# CommitV2_0.net
KiCad netlist of a schematic drawn in Altium Designer
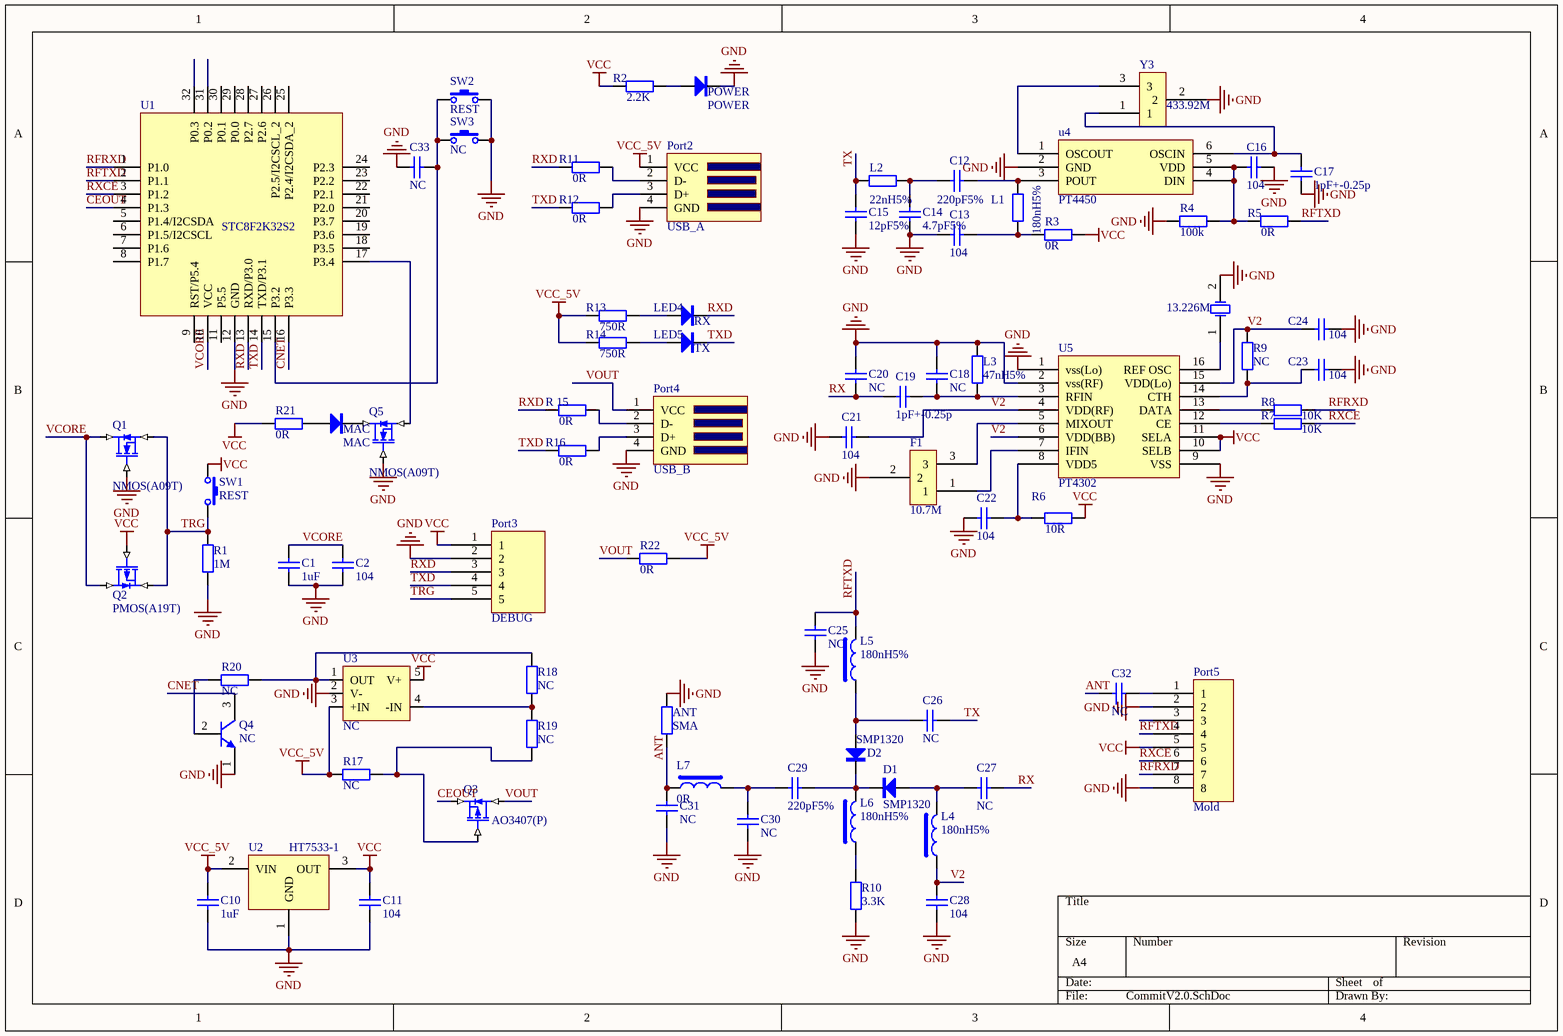
[diagram p0: CommitV2.0.SchDoc]

(export (version "E")
  (design (tool "Eeschema 10.0.6"))
  (components
    (comp (ref "ANT")
      (value "SMA")
      (footprint "SWA-KE天线母座")
      (description "Resistor")
      (fields (field (name "PUBLISHER") "Altium Limited"))
      (libsource (lib "") (part "Res2_2"))
    )
    (comp (ref "C1")
      (value "1uF")
      (footprint "0603")
      (description "Capacitor")
      (fields (field (name "PUBLISHER") "Altium Limited"))
      (libsource (lib "Miscellaneous Devices") (part "Cap"))
    )
    (comp (ref "C2")
      (value "104")
      (footprint "0603")
      (description "Capacitor")
      (fields (field (name "PUBLISHER") "Altium Limited"))
      (libsource (lib "Miscellaneous Devices") (part "Cap"))
    )
    (comp (ref "C10")
      (value "1uF")
      (footprint "0603")
      (description "Capacitor")
      (fields (field (name "PUBLISHER") "Altium Limited"))
      (libsource (lib "Miscellaneous Devices") (part "Cap"))
    )
    (comp (ref "C11")
      (value "104")
      (footprint "0603")
      (description "Capacitor")
      (fields (field (name "PUBLISHER") "Altium Limited"))
      (libsource (lib "Miscellaneous Devices") (part "Cap"))
    )
    (comp (ref "C12")
      (value "220pF5%")
      (footprint "0603")
      (description "Capacitor")
      (fields (field (name "PUBLISHER") "Altium Limited"))
      (libsource (lib "Miscellaneous Devices") (part "Cap"))
    )
    (comp (ref "C13")
      (value "104")
      (footprint "0603")
      (description "Capacitor")
      (fields (field (name "PUBLISHER") "Altium Limited"))
      (libsource (lib "Miscellaneous Devices") (part "Cap"))
    )
    (comp (ref "C14")
      (value "4.7pF5%")
      (footprint "0603")
      (description "Capacitor")
      (fields (field (name "PUBLISHER") "Altium Limited"))
      (libsource (lib "Miscellaneous Devices") (part "Cap"))
    )
    (comp (ref "C15")
      (value "12pF5%")
      (footprint "0603")
      (description "Capacitor")
      (fields (field (name "PUBLISHER") "Altium Limited"))
      (libsource (lib "Miscellaneous Devices") (part "Cap"))
    )
    (comp (ref "C16")
      (value "104")
      (footprint "0603")
      (description "Capacitor")
      (fields (field (name "PUBLISHER") "Altium Limited"))
      (libsource (lib "Miscellaneous Devices") (part "Cap"))
    )
    (comp (ref "C17")
      (value "1pF+-0.25p")
      (footprint "0603")
      (description "Capacitor")
      (fields (field (name "PUBLISHER") "Altium Limited"))
      (libsource (lib "Miscellaneous Devices") (part "Cap"))
    )
    (comp (ref "C18")
      (value "NC")
      (footprint "0603")
      (description "Capacitor")
      (fields (field (name "PUBLISHER") "Altium Limited"))
      (libsource (lib "Miscellaneous Devices") (part "Cap"))
    )
    (comp (ref "C19")
      (value "1pF+-0.25p")
      (footprint "0603")
      (description "Capacitor")
      (fields (field (name "PUBLISHER") "Altium Limited"))
      (libsource (lib "Miscellaneous Devices") (part "Cap"))
    )
    (comp (ref "C20")
      (value "NC")
      (footprint "0603")
      (description "Capacitor")
      (fields (field (name "PUBLISHER") "Altium Limited"))
      (libsource (lib "Miscellaneous Devices") (part "Cap"))
    )
    (comp (ref "C21")
      (value "104")
      (footprint "0603")
      (description "Capacitor")
      (fields (field (name "PUBLISHER") "Altium Limited"))
      (libsource (lib "Miscellaneous Devices") (part "Cap"))
    )
    (comp (ref "C22")
      (value "104")
      (footprint "0603")
      (description "Capacitor")
      (fields (field (name "PUBLISHER") "Altium Limited"))
      (libsource (lib "Miscellaneous Devices") (part "Cap"))
    )
    (comp (ref "C23")
      (value "104")
      (footprint "0603")
      (description "Capacitor")
      (fields (field (name "PUBLISHER") "Altium Limited"))
      (libsource (lib "Miscellaneous Devices") (part "Cap"))
    )
    (comp (ref "C24")
      (value "104")
      (footprint "0603")
      (description "Capacitor")
      (fields (field (name "PUBLISHER") "Altium Limited"))
      (libsource (lib "Miscellaneous Devices") (part "Cap"))
    )
    (comp (ref "C25")
      (value "NC")
      (footprint "0603")
      (description "Capacitor")
      (fields (field (name "PUBLISHER") "Altium Limited"))
      (libsource (lib "Miscellaneous Devices") (part "Cap"))
    )
    (comp (ref "C26")
      (value "NC")
      (footprint "0603")
      (description "Capacitor")
      (fields (field (name "PUBLISHER") "Altium Limited"))
      (libsource (lib "Miscellaneous Devices") (part "Cap"))
    )
    (comp (ref "C27")
      (value "NC")
      (footprint "0603")
      (description "Capacitor")
      (fields (field (name "PUBLISHER") "Altium Limited"))
      (libsource (lib "Miscellaneous Devices") (part "Cap"))
    )
    (comp (ref "C28")
      (value "104")
      (footprint "0603")
      (description "Capacitor")
      (fields (field (name "PUBLISHER") "Altium Limited"))
      (libsource (lib "Miscellaneous Devices") (part "Cap"))
    )
    (comp (ref "C29")
      (value "220pF5%")
      (footprint "0603")
      (description "Capacitor")
      (fields (field (name "PUBLISHER") "Altium Limited"))
      (libsource (lib "Miscellaneous Devices") (part "Cap"))
    )
    (comp (ref "C30")
      (value "NC")
      (footprint "0603")
      (description "Capacitor")
      (fields (field (name "PUBLISHER") "Altium Limited"))
      (libsource (lib "Miscellaneous Devices") (part "Cap"))
    )
    (comp (ref "C31")
      (value "NC")
      (footprint "0603")
      (description "Capacitor")
      (fields (field (name "PUBLISHER") "Altium Limited"))
      (libsource (lib "Miscellaneous Devices") (part "Cap"))
    )
    (comp (ref "C32")
      (value "NC")
      (footprint "0603")
      (description "Capacitor")
      (fields (field (name "PUBLISHER") "Altium Limited"))
      (libsource (lib "Miscellaneous Devices") (part "Cap"))
    )
    (comp (ref "C33")
      (value "NC")
      (footprint "0603")
      (description "Capacitor")
      (fields (field (name "PUBLISHER") "Altium Limited"))
      (libsource (lib "Miscellaneous Devices") (part "Cap"))
    )
    (comp (ref "D1")
      (value "SMP1320")
      (footprint "0603")
      (description "diode")
      (libsource (lib "") (part "DIODE_2"))
    )
    (comp (ref "D2")
      (value "SMP1320")
      (footprint "0603")
      (description "diode")
      (libsource (lib "") (part "DIODE_1"))
    )
    (comp (ref "F1") (value "10.7M") (footprint "PT4450 XTAL") (libsource (lib "MYSHC") (part "Filter")))
    (comp (ref "L1")
      (value "180nH5%")
      (footprint "0603")
      (description "Resistor")
      (fields (field (name "PUBLISHER") "Altium Limited"))
      (libsource (lib "Miscellaneous Devices") (part "Res2"))
    )
    (comp (ref "L2")
      (value "22nH5%")
      (footprint "0603")
      (description "Resistor")
      (fields (field (name "PUBLISHER") "Altium Limited"))
      (libsource (lib "") (part "Res2_3"))
    )
    (comp (ref "L3")
      (value "47nH5%")
      (footprint "0603")
      (description "Resistor")
      (fields (field (name "PUBLISHER") "Altium Limited"))
      (libsource (lib "") (part "Res2_2"))
    )
    (comp (ref "L4")
      (value "180nH5%")
      (footprint "0603")
      (description "Inductor")
      (libsource (lib "") (part "L_1"))
    )
    (comp (ref "L5")
      (value "180nH5%")
      (footprint "0603")
      (description "Inductor")
      (libsource (lib "") (part "L_1"))
    )
    (comp (ref "L6")
      (value "180nH5%")
      (footprint "0603")
      (description "Inductor")
      (libsource (lib "") (part "L_1"))
    )
    (comp (ref "L7")
      (value "0R")
      (footprint "0603")
      (description "Inductor")
      (libsource (lib "dajiang SCH -DXP") (part "L"))
    )
    (comp (ref "LED4")
      (value "RX")
      (footprint "LED-0603")
      (description "diode")
      (libsource (lib "dajiang SCH -DXP") (part "DIODE"))
    )
    (comp (ref "LED5")
      (value "TX")
      (footprint "LED-0603")
      (description "diode")
      (libsource (lib "dajiang SCH -DXP") (part "DIODE"))
    )
    (comp (ref "MAC")
      (value "MAC")
      (footprint "2.54LED")
      (description "diode")
      (libsource (lib "dajiang SCH -DXP") (part "DIODE"))
    )
    (comp (ref "Port2") (value "USB_A") (footprint "USB-A") (libsource (lib "mylib") (part "USB")))
    (comp (ref "Port3") (value "DEBUG") (footprint "STC_DEBUG") (libsource (lib "MYSHC") (part "PIN-5")))
    (comp (ref "Port4") (value "USB_B") (footprint "USB-A") (libsource (lib "mylib") (part "USB")))
    (comp (ref "Port5") (value "Mold") (footprint "Pin-8") (libsource (lib "MYSHC") (part "Pin-8")))
    (comp (ref "POWER")
      (value "POWER")
      (footprint "2.54LED")
      (description "diode")
      (libsource (lib "dajiang SCH -DXP") (part "DIODE"))
    )
    (comp (ref "Q1")
      (value "NMOS(A09T)")
      (footprint "SOT-23")
      (description "mosfet")
      (libsource (lib "dajiang SCH -DXP") (part "MOSFET-N"))
    )
    (comp (ref "Q2")
      (value "PMOS(A19T)")
      (footprint "SOT-23")
      (description "mosfet")
      (libsource (lib "dajiang SCH -DXP") (part "MOSFET-P"))
    )
    (comp (ref "Q3")
      (value "AO3407(P)")
      (footprint "SOT-23")
      (description "mosfet")
      (libsource (lib "dajiang SCH -DXP") (part "MOSFET-P"))
    )
    (comp (ref "Q4")
      (value "NC")
      (footprint "SOT-23")
      (description "NPN General Purpose Amplifier")
      (fields (field (name "PUBLISHER") "Altium Limited"))
      (libsource (lib "DT-852A(3)") (part "2N3904"))
    )
    (comp (ref "Q5")
      (value "NMOS(A09T)")
      (footprint "SOT-23")
      (description "mosfet")
      (libsource (lib "dajiang SCH -DXP") (part "MOSFET-N"))
    )
    (comp (ref "R 15")
      (value "0R")
      (footprint "0603")
      (description "Resistor")
      (fields (field (name "PUBLISHER") "Altium Limited"))
      (libsource (lib "") (part "Res2_1"))
    )
    (comp (ref "R1")
      (value "1M")
      (footprint "0603")
      (description "Resistor")
      (fields (field (name "PUBLISHER") "Altium Limited"))
      (libsource (lib "") (part "Res2_2"))
    )
    (comp (ref "R2")
      (value "2.2K")
      (footprint "0603")
      (description "Resistor")
      (fields (field (name "PUBLISHER") "Altium Limited"))
      (libsource (lib "") (part "Res2_1"))
    )
    (comp (ref "R3")
      (value "0R")
      (footprint "0603")
      (description "Resistor")
      (fields (field (name "PUBLISHER") "Altium Limited"))
      (libsource (lib "") (part "Res2_1"))
    )
    (comp (ref "R4")
      (value "100k")
      (footprint "0603")
      (description "Resistor")
      (fields (field (name "PUBLISHER") "Altium Limited"))
      (libsource (lib "") (part "Res2_1"))
    )
    (comp (ref "R5")
      (value "0R")
      (footprint "0603")
      (description "Resistor")
      (fields (field (name "PUBLISHER") "Altium Limited"))
      (libsource (lib "") (part "Res2_1"))
    )
    (comp (ref "R6")
      (value "10R")
      (footprint "0603")
      (description "Resistor")
      (fields (field (name "PUBLISHER") "Altium Limited"))
      (libsource (lib "") (part "Res2_1"))
    )
    (comp (ref "R7")
      (value "10K")
      (footprint "0603")
      (description "Resistor")
      (fields (field (name "PUBLISHER") "Altium Limited"))
      (libsource (lib "") (part "Res2_1"))
    )
    (comp (ref "R8")
      (value "10K")
      (footprint "0603")
      (description "Resistor")
      (fields (field (name "PUBLISHER") "Altium Limited"))
      (libsource (lib "") (part "Res2_1"))
    )
    (comp (ref "R9")
      (value "NC")
      (footprint "0603")
      (description "Resistor")
      (fields (field (name "PUBLISHER") "Altium Limited"))
      (libsource (lib "Miscellaneous Devices") (part "Res2"))
    )
    (comp (ref "R10")
      (value "3.3K")
      (footprint "0603")
      (description "Resistor")
      (fields (field (name "PUBLISHER") "Altium Limited"))
      (libsource (lib "Miscellaneous Devices") (part "Res2"))
    )
    (comp (ref "R11")
      (value "0R")
      (footprint "0603")
      (description "Resistor")
      (fields (field (name "PUBLISHER") "Altium Limited"))
      (libsource (lib "") (part "Res2_1"))
    )
    (comp (ref "R12")
      (value "0R")
      (footprint "0603")
      (description "Resistor")
      (fields (field (name "PUBLISHER") "Altium Limited"))
      (libsource (lib "") (part "Res2_1"))
    )
    (comp (ref "R13")
      (value "750R")
      (footprint "0603")
      (description "Resistor")
      (fields (field (name "PUBLISHER") "Altium Limited"))
      (libsource (lib "") (part "Res2_1"))
    )
    (comp (ref "R14")
      (value "750R")
      (footprint "0603")
      (description "Resistor")
      (fields (field (name "PUBLISHER") "Altium Limited"))
      (libsource (lib "") (part "Res2_1"))
    )
    (comp (ref "R16")
      (value "0R")
      (footprint "0603")
      (description "Resistor")
      (fields (field (name "PUBLISHER") "Altium Limited"))
      (libsource (lib "") (part "Res2_1"))
    )
    (comp (ref "R17")
      (value "NC")
      (footprint "0603")
      (description "Resistor")
      (fields (field (name "PUBLISHER") "Altium Limited"))
      (libsource (lib "") (part "Res2_1"))
    )
    (comp (ref "R18")
      (value "NC")
      (footprint "0603")
      (description "Resistor")
      (fields (field (name "PUBLISHER") "Altium Limited"))
      (libsource (lib "") (part "Res2_2"))
    )
    (comp (ref "R19")
      (value "NC")
      (footprint "0603")
      (description "Resistor")
      (fields (field (name "PUBLISHER") "Altium Limited"))
      (libsource (lib "") (part "Res2_2"))
    )
    (comp (ref "R20")
      (value "NC")
      (footprint "0603")
      (description "Resistor")
      (fields (field (name "PUBLISHER") "Altium Limited"))
      (libsource (lib "") (part "Res2_1"))
    )
    (comp (ref "R21")
      (value "0R")
      (footprint "0603")
      (description "Resistor")
      (fields (field (name "PUBLISHER") "Altium Limited"))
      (libsource (lib "") (part "Res2_1"))
    )
    (comp (ref "R22")
      (value "0R")
      (footprint "0805")
      (description "Resistor")
      (fields (field (name "PUBLISHER") "Altium Limited"))
      (libsource (lib "") (part "Res2_1"))
    )
    (comp (ref "SW1")
      (value "REST")
      (footprint "SW-1")
      (description "key")
      (libsource (lib "dajiang SCH -DXP") (part "SW-P"))
    )
    (comp (ref "SW2")
      (value "REST")
      (footprint "Key1")
      (description "key")
      (libsource (lib "dajiang SCH -DXP") (part "SW-P"))
    )
    (comp (ref "SW3")
      (value "NC")
      (footprint "Key1")
      (description "key")
      (libsource (lib "dajiang SCH -DXP") (part "SW-P"))
    )
    (comp (ref "U1")
      (value "STC8F2K32S2")
      (footprint "LQPF-32")
      (libsource (lib "mylib") (part "STC8F2K64S2"))
    )
    (comp (ref "U2") (value "HT7533-1") (footprint "3A5A3D") (libsource (lib "mylib") (part "HT7533-1")))
    (comp (ref "U3") (value "NC") (footprint "AD8628") (libsource (lib "*") (part "AD8628")))
    (comp (ref "u4") (value "PT4450") (libsource (lib "MYSHC") (part "PT4450")))
    (comp (ref "U5") (value "PT4302") (footprint "PT4302") (libsource (lib "MYSHC") (part "PT4302")))
    (comp (ref "Y3")
      (value "433.92M")
      (footprint "PT4450 XTAL")
      (libsource (lib "MYSHC") (part "PT4450-XTAL"))
    )
    (comp (ref "Y4")
      (value "13.226M")
      (footprint "PT4306 XTAL")
      (description "Crystal Oscillator")
      (libsource (lib "DT-852A(3)") (part "XTAL"))
    )
  )
  (nets
    (net (code "1") (name "/ANT") (class "Default")
      (node (ref "ANT") (pin "1") (pinfunction "1_1") (pintype "passive"))
      (node (ref "C31") (pin "1") (pinfunction "1_1") (pintype "passive"))
      (node (ref "C32") (pin "1") (pinfunction "1_1") (pintype "passive"))
      (node (ref "L7") (pin "1") (pinfunction "1_1") (pintype "passive"))
    )
    (net (code "2") (name "/CEOUT") (class "Default")
      (node (ref "Q3") (pin "2") (pinfunction "S_2") (pintype "input"))
      (node (ref "U1") (pin "4") (pinfunction "P1.3_4") (pintype "passive"))
    )
    (net (code "3") (name "/CNET") (class "Default")
      (node (ref "Q4") (pin "3") (pinfunction "C_3") (pintype "passive"))
      (node (ref "U1") (pin "16") (pinfunction "P3.3_16") (pintype "passive"))
    )
    (net (code "4") (name "/RFRXD") (class "Default")
      (node (ref "Port5") (pin "7") (pinfunction "7_7") (pintype "passive"))
      (node (ref "R8") (pin "1") (pinfunction "1_1") (pintype "passive"))
      (node (ref "U1") (pin "1") (pinfunction "P1.0_1") (pintype "passive"))
    )
    (net (code "5") (name "/RFTXD") (class "Default")
      (node (ref "C25") (pin "1") (pinfunction "1_1") (pintype "passive"))
      (node (ref "L5") (pin "2") (pinfunction "2_2") (pintype "passive"))
      (node (ref "Port5") (pin "4") (pinfunction "4_4") (pintype "passive"))
      (node (ref "R5") (pin "1") (pinfunction "1_1") (pintype "passive"))
      (node (ref "U1") (pin "2") (pinfunction "P1.1_2") (pintype "passive"))
    )
    (net (code "6") (name "/RX") (class "Default")
      (node (ref "C19") (pin "1") (pinfunction "1_1") (pintype "passive"))
      (node (ref "C20") (pin "1") (pinfunction "1_1") (pintype "passive"))
      (node (ref "C27") (pin "2") (pinfunction "2_2") (pintype "passive"))
    )
    (net (code "7") (name "/RXCE") (class "Default")
      (node (ref "Port5") (pin "6") (pinfunction "6_6") (pintype "passive"))
      (node (ref "R7") (pin "1") (pinfunction "1_1") (pintype "passive"))
      (node (ref "U1") (pin "3") (pinfunction "P1.2_3") (pintype "passive"))
    )
    (net (code "8") (name "/RXD") (class "Default")
      (node (ref "LED4") (pin "2") (pinfunction "2_2") (pintype "passive"))
      (node (ref "Port3") (pin "3") (pinfunction "3_3") (pintype "passive"))
      (node (ref "R 15") (pin "2") (pinfunction "2_2") (pintype "passive"))
      (node (ref "R11") (pin "2") (pinfunction "2_2") (pintype "passive"))
      (node (ref "U1") (pin "13") (pinfunction "RXD/P3.0_13") (pintype "passive"))
    )
    (net (code "9") (name "/TRG") (class "Default")
      (node (ref "Port3") (pin "5") (pinfunction "5_5") (pintype "passive"))
      (node (ref "Q1") (pin "2") (pinfunction "D_2") (pintype "input"))
      (node (ref "Q2") (pin "2") (pinfunction "S_2") (pintype "input"))
      (node (ref "R1") (pin "2") (pinfunction "2_2") (pintype "passive"))
      (node (ref "SW1") (pin "2") (pinfunction "2_2") (pintype "passive"))
    )
    (net (code "10") (name "/TX") (class "Default")
      (node (ref "C15") (pin "2") (pinfunction "2_2") (pintype "passive"))
      (node (ref "C26") (pin "2") (pinfunction "2_2") (pintype "passive"))
      (node (ref "L2") (pin "1") (pinfunction "1_1") (pintype "passive"))
    )
    (net (code "11") (name "/TXD") (class "Default")
      (node (ref "LED5") (pin "2") (pinfunction "2_2") (pintype "passive"))
      (node (ref "Port3") (pin "4") (pinfunction "4_4") (pintype "passive"))
      (node (ref "R12") (pin "2") (pinfunction "2_2") (pintype "passive"))
      (node (ref "R16") (pin "2") (pinfunction "2_2") (pintype "passive"))
      (node (ref "U1") (pin "14") (pinfunction "TXD/P3.1_14") (pintype "passive"))
    )
    (net (code "12") (name "/V2") (class "Default")
      (node (ref "C21") (pin "1") (pinfunction "1_1") (pintype "passive"))
      (node (ref "C24") (pin "2") (pinfunction "2_2") (pintype "passive"))
      (node (ref "C28") (pin "2") (pinfunction "2_2") (pintype "passive"))
      (node (ref "L4") (pin "1") (pinfunction "1_1") (pintype "passive"))
      (node (ref "R9") (pin "1") (pinfunction "1_1") (pintype "passive"))
      (node (ref "U5") (pin "15") (pinfunction "VDD(Lo)_15") (pintype "passive"))
      (node (ref "U5") (pin "4") (pinfunction "VDD(RF)_4") (pintype "passive"))
      (node (ref "U5") (pin "6") (pinfunction "VDD(BB)_6") (pintype "passive"))
    )
    (net (code "13") (name "/VCORE") (class "Default")
      (node (ref "C1") (pin "2") (pinfunction "2_2") (pintype "passive"))
      (node (ref "C2") (pin "2") (pinfunction "2_2") (pintype "passive"))
      (node (ref "Q1") (pin "3") (pinfunction "S_3") (pintype "input"))
      (node (ref "Q2") (pin "3") (pinfunction "D_3") (pintype "input"))
      (node (ref "U1") (pin "10") (pinfunction "VCC_10") (pintype "passive"))
    )
    (net (code "14") (name "/VOUT") (class "Default")
      (node (ref "Port4") (pin "1") (pinfunction "VCC_1") (pintype "passive"))
      (node (ref "Q3") (pin "3") (pinfunction "D_3") (pintype "input"))
      (node (ref "R22") (pin "2") (pinfunction "2_2") (pintype "passive"))
    )
    (net (code "15") (name "GND") (class "Default")
      (node (ref "ANT") (pin "2") (pinfunction "2_2") (pintype "passive"))
      (node (ref "C1") (pin "1") (pinfunction "1_1") (pintype "passive"))
      (node (ref "C10") (pin "2") (pinfunction "2_2") (pintype "passive"))
      (node (ref "C11") (pin "2") (pinfunction "2_2") (pintype "passive"))
      (node (ref "C13") (pin "1") (pinfunction "1_1") (pintype "passive"))
      (node (ref "C14") (pin "1") (pinfunction "1_1") (pintype "passive"))
      (node (ref "C15") (pin "1") (pinfunction "1_1") (pintype "passive"))
      (node (ref "C16") (pin "1") (pinfunction "1_1") (pintype "passive"))
      (node (ref "C17") (pin "2") (pinfunction "2_2") (pintype "passive"))
      (node (ref "C18") (pin "1") (pinfunction "1_1") (pintype "passive"))
      (node (ref "C2") (pin "1") (pinfunction "1_1") (pintype "passive"))
      (node (ref "C20") (pin "2") (pinfunction "2_2") (pintype "passive"))
      (node (ref "C21") (pin "2") (pinfunction "2_2") (pintype "passive"))
      (node (ref "C22") (pin "2") (pinfunction "2_2") (pintype "passive"))
      (node (ref "C23") (pin "1") (pinfunction "1_1") (pintype "passive"))
      (node (ref "C24") (pin "1") (pinfunction "1_1") (pintype "passive"))
      (node (ref "C25") (pin "2") (pinfunction "2_2") (pintype "passive"))
      (node (ref "C28") (pin "1") (pinfunction "1_1") (pintype "passive"))
      (node (ref "C30") (pin "2") (pinfunction "2_2") (pintype "passive"))
      (node (ref "C31") (pin "2") (pinfunction "2_2") (pintype "passive"))
      (node (ref "C33") (pin "1") (pinfunction "1_1") (pintype "passive"))
      (node (ref "F1") (pin "2") (pinfunction "2_2") (pintype "passive"))
      (node (ref "L3") (pin "2") (pinfunction "2_2") (pintype "passive"))
      (node (ref "POWER") (pin "2") (pinfunction "2_2") (pintype "passive"))
      (node (ref "Port2") (pin "4") (pinfunction "GND_4") (pintype "passive"))
      (node (ref "Port3") (pin "2") (pinfunction "2_2") (pintype "passive"))
      (node (ref "Port4") (pin "4") (pinfunction "GND_4") (pintype "passive"))
      (node (ref "Port5") (pin "2") (pinfunction "2_2") (pintype "passive"))
      (node (ref "Port5") (pin "8") (pinfunction "8_8") (pintype "passive"))
      (node (ref "Q1") (pin "1") (pinfunction "G_1") (pintype "input"))
      (node (ref "Q4") (pin "1") (pinfunction "E_1") (pintype "passive"))
      (node (ref "Q5") (pin "1") (pinfunction "G_1") (pintype "input"))
      (node (ref "R1") (pin "1") (pinfunction "1_1") (pintype "passive"))
      (node (ref "R10") (pin "2") (pinfunction "2_2") (pintype "passive"))
      (node (ref "R4") (pin "2") (pinfunction "2_2") (pintype "passive"))
      (node (ref "SW2") (pin "2") (pinfunction "2_2") (pintype "passive"))
      (node (ref "SW3") (pin "2") (pinfunction "2_2") (pintype "passive"))
      (node (ref "U1") (pin "12") (pinfunction "GND_12") (pintype "passive"))
      (node (ref "U2") (pin "1") (pinfunction "GND_1") (pintype "passive"))
      (node (ref "U3") (pin "2") (pinfunction "V-_2") (pintype "passive"))
      (node (ref "U5") (pin "1") (pinfunction "vss(Lo)_1") (pintype "passive"))
      (node (ref "U5") (pin "2") (pinfunction "vss(RF)_2") (pintype "passive"))
      (node (ref "U5") (pin "9") (pinfunction "VSS_9") (pintype "passive"))
      (node (ref "Y3") (pin "2") (pinfunction "2_2") (pintype "passive"))
      (node (ref "Y4") (pin "2") (pinfunction "OSC2_2") (pintype "passive"))
      (node (ref "u4") (pin "2") (pinfunction "GND_2") (pintype "passive"))
    )
    (net (code "16") (name "Net-(C12-Pad1)") (class "Default")
      (node (ref "C12") (pin "1") (pinfunction "1_1") (pintype "passive"))
      (node (ref "C14") (pin "2") (pinfunction "2_2") (pintype "passive"))
      (node (ref "L2") (pin "2") (pinfunction "2_2") (pintype "passive"))
    )
    (net (code "17") (name "Net-(C13-Pad2)") (class "Default")
      (node (ref "C13") (pin "2") (pinfunction "2_2") (pintype "passive"))
      (node (ref "L1") (pin "2") (pinfunction "2_2") (pintype "passive"))
      (node (ref "R3") (pin "2") (pinfunction "2_2") (pintype "passive"))
    )
    (net (code "18") (name "Net-(C26-Pad1)") (class "Default")
      (node (ref "C26") (pin "1") (pinfunction "1_1") (pintype "passive"))
      (node (ref "D2") (pin "1") (pinfunction "1_1") (pintype "passive"))
      (node (ref "L5") (pin "1") (pinfunction "1_1") (pintype "passive"))
    )
    (net (code "19") (name "Net-(C27-Pad1)") (class "Default")
      (node (ref "C27") (pin "1") (pinfunction "1_1") (pintype "passive"))
      (node (ref "D1") (pin "1") (pinfunction "1_1") (pintype "passive"))
      (node (ref "L4") (pin "2") (pinfunction "2_2") (pintype "passive"))
    )
    (net (code "20") (name "Net-(C29-Pad1)") (class "Default")
      (node (ref "C29") (pin "1") (pinfunction "1_1") (pintype "passive"))
      (node (ref "D1") (pin "2") (pinfunction "2_2") (pintype "passive"))
      (node (ref "D2") (pin "2") (pinfunction "2_2") (pintype "passive"))
      (node (ref "L6") (pin "2") (pinfunction "2_2") (pintype "passive"))
    )
    (net (code "21") (name "Net-(C29-Pad2)") (class "Default")
      (node (ref "C29") (pin "2") (pinfunction "2_2") (pintype "passive"))
      (node (ref "C30") (pin "1") (pinfunction "1_1") (pintype "passive"))
      (node (ref "L7") (pin "2") (pinfunction "2_2") (pintype "passive"))
    )
    (net (code "22") (name "Net-(C32-Pad2)") (class "Default")
      (node (ref "C32") (pin "2") (pinfunction "2_2") (pintype "passive"))
      (node (ref "Port5") (pin "1") (pinfunction "1_1") (pintype "passive"))
    )
    (net (code "23") (name "Net-(L6-Pad1)") (class "Default")
      (node (ref "L6") (pin "1") (pinfunction "1_1") (pintype "passive"))
      (node (ref "R10") (pin "1") (pinfunction "1_1") (pintype "passive"))
    )
    (net (code "24") (name "Net-(LED4-Pad1)") (class "Default")
      (node (ref "LED4") (pin "1") (pinfunction "1_1") (pintype "passive"))
      (node (ref "R13") (pin "1") (pinfunction "1_1") (pintype "passive"))
    )
    (net (code "25") (name "Net-(LED5-Pad1)") (class "Default")
      (node (ref "LED5") (pin "1") (pinfunction "1_1") (pintype "passive"))
      (node (ref "R14") (pin "1") (pinfunction "1_1") (pintype "passive"))
    )
    (net (code "26") (name "Net-(MAC-Pad1)") (class "Default")
      (node (ref "MAC") (pin "1") (pinfunction "1_1") (pintype "passive"))
      (node (ref "R21") (pin "1") (pinfunction "1_1") (pintype "passive"))
    )
    (net (code "27") (name "Net-(POWER-Pad1)") (class "Default")
      (node (ref "POWER") (pin "1") (pinfunction "1_1") (pintype "passive"))
      (node (ref "R2") (pin "1") (pinfunction "1_1") (pintype "passive"))
    )
    (net (code "28") (name "Net-(Port2-D+)") (class "Default")
      (node (ref "Port2") (pin "3") (pinfunction "D+_3") (pintype "passive"))
      (node (ref "R12") (pin "1") (pinfunction "1_1") (pintype "passive"))
    )
    (net (code "29") (name "Net-(Port2-D-)") (class "Default")
      (node (ref "Port2") (pin "2") (pinfunction "D-_2") (pintype "passive"))
      (node (ref "R11") (pin "1") (pinfunction "1_1") (pintype "passive"))
    )
    (net (code "30") (name "Net-(Port4-D+)") (class "Default")
      (node (ref "Port4") (pin "3") (pinfunction "D+_3") (pintype "passive"))
      (node (ref "R16") (pin "1") (pinfunction "1_1") (pintype "passive"))
    )
    (net (code "31") (name "Net-(Port4-D-)") (class "Default")
      (node (ref "Port4") (pin "2") (pinfunction "D-_2") (pintype "passive"))
      (node (ref "R 15") (pin "1") (pinfunction "1_1") (pintype "passive"))
    )
    (net (code "32") (name "Net-(Q3-G)") (class "Default")
      (node (ref "Q3") (pin "1") (pinfunction "G_1") (pintype "input"))
      (node (ref "R17") (pin "1") (pinfunction "1_1") (pintype "passive"))
      (node (ref "R19") (pin "1") (pinfunction "1_1") (pintype "passive"))
    )
    (net (code "33") (name "Net-(Q4-B)") (class "Default")
      (node (ref "Q4") (pin "2") (pinfunction "B_2") (pintype "passive"))
      (node (ref "R20") (pin "2") (pinfunction "2_2") (pintype "passive"))
    )
    (net (code "34") (name "Net-(Q5-D)") (class "Default")
      (node (ref "Q5") (pin "2") (pinfunction "D_2") (pintype "input"))
      (node (ref "U1") (pin "17") (pinfunction "P3.4_17") (pintype "passive"))
    )
    (net (code "35") (name "Net-(Q5-S)") (class "Default")
      (node (ref "MAC") (pin "2") (pinfunction "2_2") (pintype "passive"))
      (node (ref "Q5") (pin "3") (pinfunction "S_3") (pintype "input"))
    )
    (net (code "36") (name "Net-(U1-P3.2)") (class "Default")
      (node (ref "C33") (pin "2") (pinfunction "2_2") (pintype "passive"))
      (node (ref "SW2") (pin "1") (pinfunction "1_1") (pintype "passive"))
      (node (ref "SW3") (pin "1") (pinfunction "1_1") (pintype "passive"))
      (node (ref "U1") (pin "15") (pinfunction "P3.2_15") (pintype "passive"))
    )
    (net (code "37") (name "Net-(U3--IN)") (class "Default")
      (node (ref "R18") (pin "1") (pinfunction "1_1") (pintype "passive"))
      (node (ref "R19") (pin "2") (pinfunction "2_2") (pintype "passive"))
      (node (ref "U3") (pin "4") (pinfunction "-IN_4") (pintype "passive"))
    )
    (net (code "38") (name "Net-(U3-OUT)") (class "Default")
      (node (ref "R18") (pin "2") (pinfunction "2_2") (pintype "passive"))
      (node (ref "R20") (pin "1") (pinfunction "1_1") (pintype "passive"))
      (node (ref "U3") (pin "1") (pinfunction "OUT_1") (pintype "passive"))
    )
    (net (code "39") (name "Net-(U5-CE)") (class "Default")
      (node (ref "R7") (pin "2") (pinfunction "2_2") (pintype "passive"))
      (node (ref "U5") (pin "12") (pinfunction "CE_12") (pintype "passive"))
    )
    (net (code "40") (name "Net-(U5-CTH)") (class "Default")
      (node (ref "C23") (pin "2") (pinfunction "2_2") (pintype "passive"))
      (node (ref "R9") (pin "2") (pinfunction "2_2") (pintype "passive"))
      (node (ref "U5") (pin "14") (pinfunction "CTH_14") (pintype "passive"))
    )
    (net (code "41") (name "Net-(U5-DATA)") (class "Default")
      (node (ref "R8") (pin "2") (pinfunction "2_2") (pintype "passive"))
      (node (ref "U5") (pin "13") (pinfunction "DATA_13") (pintype "passive"))
    )
    (net (code "42") (name "Net-(U5-IFIN)") (class "Default")
      (node (ref "F1") (pin "1") (pinfunction "1_1") (pintype "passive"))
      (node (ref "U5") (pin "7") (pinfunction "IFIN_7") (pintype "passive"))
    )
    (net (code "43") (name "Net-(U5-MIXOUT)") (class "Default")
      (node (ref "F1") (pin "3") (pinfunction "3_3") (pintype "passive"))
      (node (ref "U5") (pin "5") (pinfunction "MIXOUT_5") (pintype "passive"))
    )
    (net (code "44") (name "Net-(U5-REF_OSC)") (class "Default")
      (node (ref "U5") (pin "16") (pinfunction "REF_OSC_16") (pintype "passive"))
      (node (ref "Y4") (pin "1") (pinfunction "OSC1_1") (pintype "passive"))
    )
    (net (code "45") (name "Net-(U5-RFIN)") (class "Default")
      (node (ref "C18") (pin "2") (pinfunction "2_2") (pintype "passive"))
      (node (ref "C19") (pin "2") (pinfunction "2_2") (pintype "passive"))
      (node (ref "L3") (pin "1") (pinfunction "1_1") (pintype "passive"))
      (node (ref "U5") (pin "3") (pinfunction "RFIN_3") (pintype "passive"))
    )
    (net (code "46") (name "Net-(U5-VDD5)") (class "Default")
      (node (ref "C22") (pin "1") (pinfunction "1_1") (pintype "passive"))
      (node (ref "R6") (pin "2") (pinfunction "2_2") (pintype "passive"))
      (node (ref "U5") (pin "8") (pinfunction "VDD5_8") (pintype "passive"))
    )
    (net (code "47") (name "Net-(u4-DIN)") (class "Default")
      (node (ref "C16") (pin "2") (pinfunction "2_2") (pintype "passive"))
      (node (ref "R4") (pin "1") (pinfunction "1_1") (pintype "passive"))
      (node (ref "R5") (pin "2") (pinfunction "2_2") (pintype "passive"))
      (node (ref "u4") (pin "4") (pinfunction "DIN_4") (pintype "passive"))
      (node (ref "u4") (pin "5") (pinfunction "VDD_5") (pintype "passive"))
    )
    (net (code "48") (name "Net-(u4-OSCIN)") (class "Default")
      (node (ref "C17") (pin "1") (pinfunction "1_1") (pintype "passive"))
      (node (ref "Y3") (pin "1") (pinfunction "1_1") (pintype "passive"))
      (node (ref "u4") (pin "6") (pinfunction "OSCIN_6") (pintype "passive"))
    )
    (net (code "49") (name "Net-(u4-OSCOUT)") (class "Default")
      (node (ref "Y3") (pin "3") (pinfunction "3_3") (pintype "passive"))
      (node (ref "u4") (pin "1") (pinfunction "OSCOUT_1") (pintype "passive"))
    )
    (net (code "50") (name "Net-(u4-POUT)") (class "Default")
      (node (ref "C12") (pin "2") (pinfunction "2_2") (pintype "passive"))
      (node (ref "L1") (pin "1") (pinfunction "1_1") (pintype "passive"))
      (node (ref "u4") (pin "3") (pinfunction "POUT_3") (pintype "passive"))
    )
    (net (code "51") (name "VCC") (class "Default")
      (node (ref "C11") (pin "1") (pinfunction "1_1") (pintype "passive"))
      (node (ref "Port3") (pin "1") (pinfunction "1_1") (pintype "passive"))
      (node (ref "Port5") (pin "5") (pinfunction "5_5") (pintype "passive"))
      (node (ref "Q2") (pin "1") (pinfunction "G_1") (pintype "input"))
      (node (ref "R2") (pin "2") (pinfunction "2_2") (pintype "passive"))
      (node (ref "R21") (pin "2") (pinfunction "2_2") (pintype "passive"))
      (node (ref "R3") (pin "1") (pinfunction "1_1") (pintype "passive"))
      (node (ref "R6") (pin "1") (pinfunction "1_1") (pintype "passive"))
      (node (ref "SW1") (pin "1") (pinfunction "1_1") (pintype "passive"))
      (node (ref "U2") (pin "3") (pinfunction "OUT_3") (pintype "passive"))
      (node (ref "U3") (pin "5") (pinfunction "V+_5") (pintype "passive"))
      (node (ref "U5") (pin "10") (pinfunction "SELB_10") (pintype "passive"))
      (node (ref "U5") (pin "11") (pinfunction "SELA_11") (pintype "passive"))
    )
    (net (code "52") (name "VCC_5V") (class "Default")
      (node (ref "C10") (pin "1") (pinfunction "1_1") (pintype "passive"))
      (node (ref "Port2") (pin "1") (pinfunction "VCC_1") (pintype "passive"))
      (node (ref "R13") (pin "2") (pinfunction "2_2") (pintype "passive"))
      (node (ref "R14") (pin "2") (pinfunction "2_2") (pintype "passive"))
      (node (ref "R17") (pin "2") (pinfunction "2_2") (pintype "passive"))
      (node (ref "R22") (pin "1") (pinfunction "1_1") (pintype "passive"))
      (node (ref "U2") (pin "2") (pinfunction "VIN_2") (pintype "passive"))
      (node (ref "U3") (pin "3") (pinfunction "+IN_3") (pintype "passive"))
    )
    (net (code "53") (name "unconnected-(Port5-Pad3)") (class "Default")
      (node (ref "Port5") (pin "3") (pinfunction "3_3") (pintype "passive"))
    )
    (net (code "54") (name "unconnected-(U1-P0.0-Pad29)") (class "Default")
      (node (ref "U1") (pin "29") (pinfunction "P0.0_29") (pintype "passive"))
    )
    (net (code "55") (name "unconnected-(U1-P0.1-Pad30)") (class "Default")
      (node (ref "U1") (pin "30") (pinfunction "P0.1_30") (pintype "passive"))
    )
    (net (code "56") (name "unconnected-(U1-P0.2-Pad31)") (class "Default")
      (node (ref "U1") (pin "31") (pinfunction "P0.2_31") (pintype "passive"))
    )
    (net (code "57") (name "unconnected-(U1-P0.3-Pad32)") (class "Default")
      (node (ref "U1") (pin "32") (pinfunction "P0.3_32") (pintype "passive"))
    )
    (net (code "58") (name "unconnected-(U1-P1.4{slash}I2CSDA-Pad5)") (class "Default")
      (node (ref "U1") (pin "5") (pinfunction "P1.4/I2CSDA_5") (pintype "passive"))
    )
    (net (code "59") (name "unconnected-(U1-P1.5{slash}I2CSCL-Pad6)") (class "Default")
      (node (ref "U1") (pin "6") (pinfunction "P1.5/I2CSCL_6") (pintype "passive"))
    )
    (net (code "60") (name "unconnected-(U1-P1.6-Pad7)") (class "Default")
      (node (ref "U1") (pin "7") (pinfunction "P1.6_7") (pintype "passive"))
    )
    (net (code "61") (name "unconnected-(U1-P1.7-Pad8)") (class "Default")
      (node (ref "U1") (pin "8") (pinfunction "P1.7_8") (pintype "passive"))
    )
    (net (code "62") (name "unconnected-(U1-P2.0-Pad21)") (class "Default")
      (node (ref "U1") (pin "21") (pinfunction "P2.0_21") (pintype "passive"))
    )
    (net (code "63") (name "unconnected-(U1-P2.1-Pad22)") (class "Default")
      (node (ref "U1") (pin "22") (pinfunction "P2.1_22") (pintype "passive"))
    )
    (net (code "64") (name "unconnected-(U1-P2.2-Pad23)") (class "Default")
      (node (ref "U1") (pin "23") (pinfunction "P2.2_23") (pintype "passive"))
    )
    (net (code "65") (name "unconnected-(U1-P2.3-Pad24)") (class "Default")
      (node (ref "U1") (pin "24") (pinfunction "P2.3_24") (pintype "passive"))
    )
    (net (code "66") (name "unconnected-(U1-P2.4{slash}I2CSDA_2-Pad25)") (class "Default")
      (node (ref "U1") (pin "25") (pinfunction "P2.4/I2CSDA_2_25") (pintype "passive"))
    )
    (net (code "67") (name "unconnected-(U1-P2.5{slash}I2CSCL_2-Pad26)") (class "Default")
      (node (ref "U1") (pin "26") (pinfunction "P2.5/I2CSCL_2_26") (pintype "passive"))
    )
    (net (code "68") (name "unconnected-(U1-P2.6-Pad27)") (class "Default")
      (node (ref "U1") (pin "27") (pinfunction "P2.6_27") (pintype "passive"))
    )
    (net (code "69") (name "unconnected-(U1-P2.7-Pad28)") (class "Default")
      (node (ref "U1") (pin "28") (pinfunction "P2.7_28") (pintype "passive"))
    )
    (net (code "70") (name "unconnected-(U1-P3.5-Pad18)") (class "Default")
      (node (ref "U1") (pin "18") (pinfunction "P3.5_18") (pintype "passive"))
    )
    (net (code "71") (name "unconnected-(U1-P3.6-Pad19)") (class "Default")
      (node (ref "U1") (pin "19") (pinfunction "P3.6_19") (pintype "passive"))
    )
    (net (code "72") (name "unconnected-(U1-P3.7-Pad20)") (class "Default")
      (node (ref "U1") (pin "20") (pinfunction "P3.7_20") (pintype "passive"))
    )
    (net (code "73") (name "unconnected-(U1-P5.5-Pad11)") (class "Default")
      (node (ref "U1") (pin "11") (pinfunction "P5.5_11") (pintype "passive"))
    )
    (net (code "74") (name "unconnected-(U1-RST{slash}P5.4-Pad9)") (class "Default")
      (node (ref "U1") (pin "9") (pinfunction "RST/P5.4_9") (pintype "passive"))
    )
  )
)
